# playC.net
KiCad netlist of a schematic drawn in Altium Designer
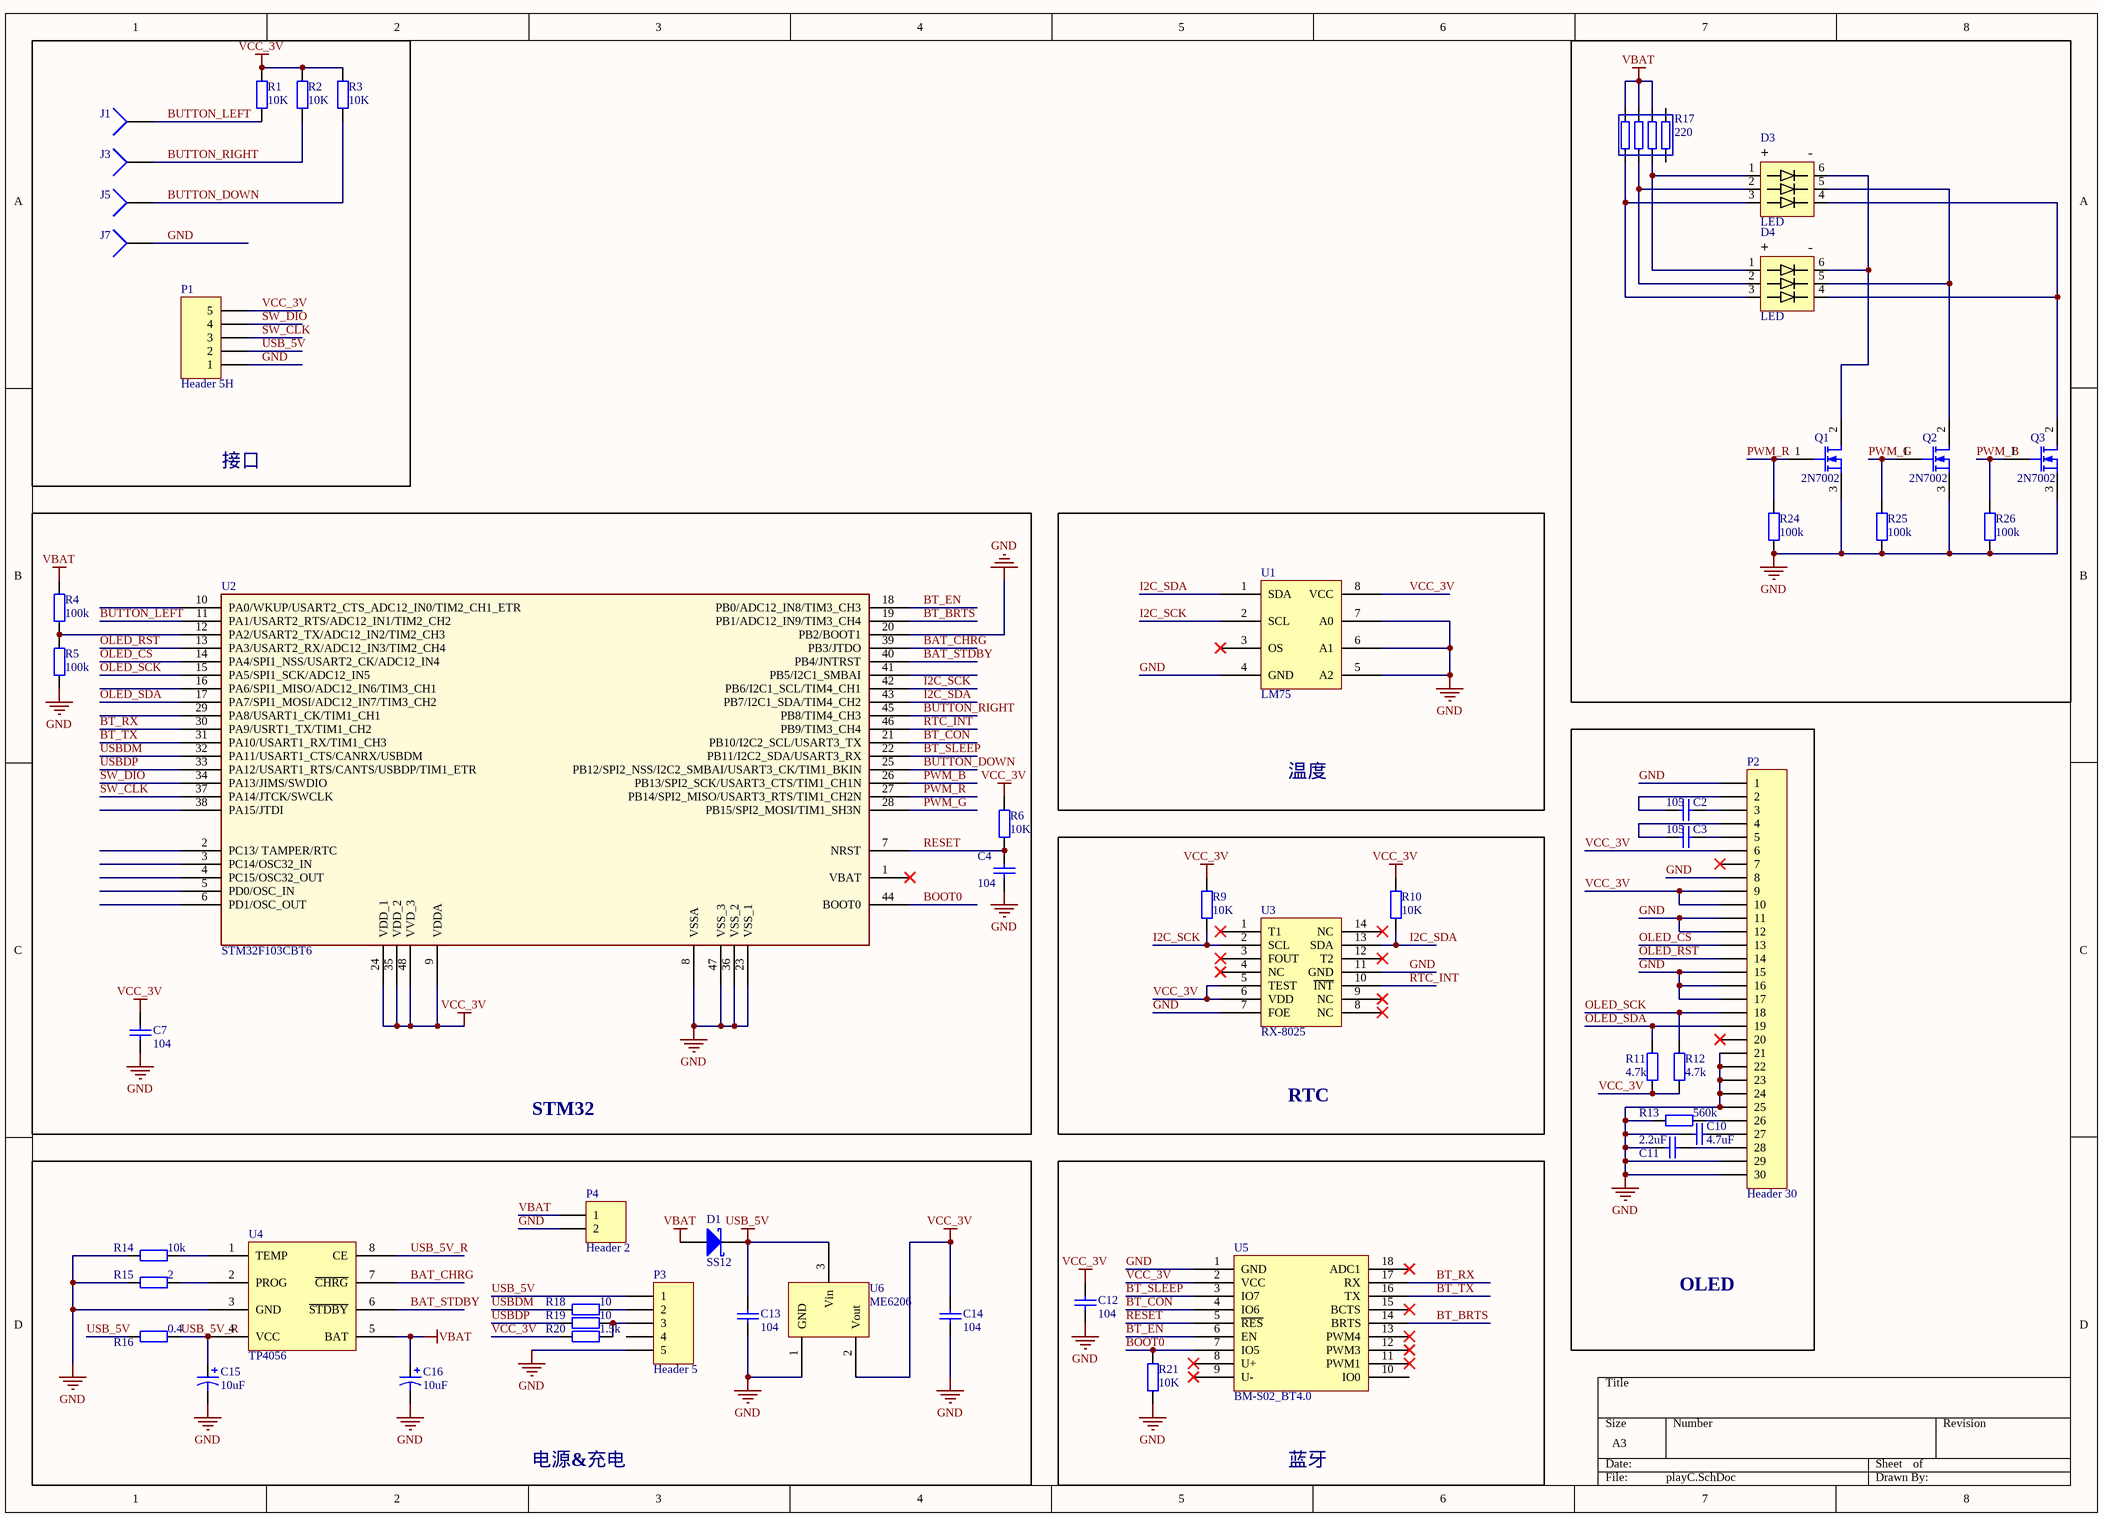
[diagram p0: playC.SchDoc]

(export (version "E")
  (design (tool "Eeschema 10.0.6"))
  (components
    (comp (ref "C2")
      (value "105")
      (footprint "0603")
      (description "Capacitor")
      (fields (field (name "PUBLISHER") "Altium Limited"))
      (libsource (lib "Miscellaneous Devices") (part "Cap"))
    )
    (comp (ref "C3")
      (value "105")
      (footprint "0603")
      (description "Capacitor")
      (fields (field (name "PUBLISHER") "Altium Limited"))
      (libsource (lib "Miscellaneous Devices") (part "Cap"))
    )
    (comp (ref "C4")
      (value "104")
      (footprint "0603")
      (description "Capacitor")
      (fields (field (name "PUBLISHER") "Altium Limited"))
      (libsource (lib "Miscellaneous Devices") (part "Cap"))
    )
    (comp (ref "C7")
      (value "104")
      (footprint "0603")
      (description "Capacitor")
      (fields (field (name "PUBLISHER") "Altium Limited"))
      (libsource (lib "Miscellaneous Devices") (part "Cap"))
    )
    (comp (ref "C10")
      (value "4.7uF")
      (footprint "0805")
      (description "Capacitor")
      (fields (field (name "PUBLISHER") "Altium Limited"))
      (libsource (lib "Miscellaneous Devices") (part "Cap"))
    )
    (comp (ref "C11")
      (value "2.2uF")
      (footprint "0805")
      (description "Capacitor")
      (fields (field (name "PUBLISHER") "Altium Limited"))
      (libsource (lib "Miscellaneous Devices") (part "Cap"))
    )
    (comp (ref "C12")
      (value "104")
      (footprint "0603")
      (description "Capacitor")
      (fields (field (name "PUBLISHER") "Altium Limited"))
      (libsource (lib "Miscellaneous Devices") (part "Cap"))
    )
    (comp (ref "C13")
      (value "104")
      (footprint "0603")
      (description "Capacitor")
      (fields (field (name "PUBLISHER") "Altium Limited"))
      (libsource (lib "Miscellaneous Devices") (part "Cap"))
    )
    (comp (ref "C14")
      (value "104")
      (footprint "0603")
      (description "Capacitor")
      (fields (field (name "PUBLISHER") "Altium Limited"))
      (libsource (lib "Miscellaneous Devices") (part "Cap"))
    )
    (comp (ref "C15")
      (value "10uF")
      (footprint "Cap_Tan_B")
      (description "Polarized Capacitor (Radial)")
      (fields (field (name "PUBLISHER") "Altium Limited"))
      (libsource (lib "Miscellaneous Devices") (part "Cap Pol1"))
    )
    (comp (ref "C16")
      (value "10uF")
      (footprint "Cap_Tan_B")
      (description "Polarized Capacitor (Radial)")
      (fields (field (name "PUBLISHER") "Altium Limited"))
      (libsource (lib "Miscellaneous Devices") (part "Cap Pol1"))
    )
    (comp (ref "D1")
      (value "SS12")
      (footprint "SMA")
      (description "Schottky Diode")
      (fields (field (name "PUBLISHER") "Altium Limited"))
      (libsource (lib "Miscellaneous Devices") (part "D Schottky"))
    )
    (comp (ref "D3") (value "LED") (footprint "5050_LED") (libsource (lib "SmartLED") (part "LED_6Pin")))
    (comp (ref "D4") (value "LED") (footprint "5050_LED") (libsource (lib "SmartLED") (part "LED_6Pin")))
    (comp (ref "J1")
      (value "PAD")
      (footprint "LINK_HOLE")
      (description "Socket")
      (fields (field (name "PUBLISHER") "Altium Limited"))
      (libsource (lib "Miscellaneous Connectors") (part "Socket"))
    )
    (comp (ref "J3")
      (value "PAD")
      (footprint "LINK_HOLE")
      (description "Socket")
      (fields (field (name "PUBLISHER") "Altium Limited"))
      (libsource (lib "Miscellaneous Connectors") (part "Socket"))
    )
    (comp (ref "J5")
      (value "PAD")
      (footprint "LINK_HOLE")
      (description "Socket")
      (fields (field (name "PUBLISHER") "Altium Limited"))
      (libsource (lib "Miscellaneous Connectors") (part "Socket"))
    )
    (comp (ref "J7")
      (value "PAD")
      (footprint "LINK_HOLE")
      (description "Socket")
      (fields (field (name "PUBLISHER") "Altium Limited"))
      (libsource (lib "Miscellaneous Connectors") (part "Socket"))
    )
    (comp (ref "P1")
      (value "Header 5H")
      (footprint "connect_5pin")
      (description "Header, 5-Pin, Right Angle")
      (fields (field (name "PUBLISHER") "Altium Limited"))
      (libsource (lib "Miscellaneous Connectors") (part "Header 5H"))
    )
    (comp (ref "P2")
      (value "Header 30")
      (footprint "OLED(30PIN_1.3')")
      (description "Header, 30-Pin")
      (fields (field (name "PUBLISHER") "Altium Limited"))
      (libsource (lib "Miscellaneous Connectors") (part "Header 30"))
    )
    (comp (ref "P3")
      (value "Header 5")
      (footprint "Mini_USB_IN")
      (description "Header, 5-Pin")
      (fields (field (name "PUBLISHER") "Altium Limited"))
      (libsource (lib "Miscellaneous Connectors") (part "Header 5"))
    )
    (comp (ref "P4")
      (value "Header 2")
      (footprint "HDR1X2")
      (description "Header, 2-Pin")
      (fields (field (name "PUBLISHER") "Altium Limited"))
      (libsource (lib "Miscellaneous Connectors") (part "Header 2"))
    )
    (comp (ref "Q1")
      (value "2N7002")
      (footprint "SOT23")
      (description "N-Channel MOSFET")
      (fields (field (name "PUBLISHER") "Altium Limited"))
      (libsource (lib "Miscellaneous Devices") (part "MOSFET-N"))
    )
    (comp (ref "Q2")
      (value "2N7002")
      (footprint "SOT23")
      (description "N-Channel MOSFET")
      (fields (field (name "PUBLISHER") "Altium Limited"))
      (libsource (lib "Miscellaneous Devices") (part "MOSFET-N"))
    )
    (comp (ref "Q3")
      (value "2N7002")
      (footprint "SOT23")
      (description "N-Channel MOSFET")
      (fields (field (name "PUBLISHER") "Altium Limited"))
      (libsource (lib "Miscellaneous Devices") (part "MOSFET-N"))
    )
    (comp (ref "R1")
      (value "10K")
      (footprint "0603")
      (description "Resistor")
      (fields (field (name "PUBLISHER") "Altium Limited"))
      (libsource (lib "Miscellaneous Devices") (part "Res2"))
    )
    (comp (ref "R2")
      (value "10K")
      (footprint "0603")
      (description "Resistor")
      (fields (field (name "PUBLISHER") "Altium Limited"))
      (libsource (lib "Miscellaneous Devices") (part "Res2"))
    )
    (comp (ref "R3")
      (value "10K")
      (footprint "0603")
      (description "Resistor")
      (fields (field (name "PUBLISHER") "Altium Limited"))
      (libsource (lib "Miscellaneous Devices") (part "Res2"))
    )
    (comp (ref "R4")
      (value "100k")
      (footprint "0603")
      (description "Resistor")
      (fields (field (name "PUBLISHER") "Altium Limited"))
      (libsource (lib "") (part "Res2_1"))
    )
    (comp (ref "R5")
      (value "100k")
      (footprint "0603")
      (description "Resistor")
      (fields (field (name "PUBLISHER") "Altium Limited"))
      (libsource (lib "") (part "Res2_1"))
    )
    (comp (ref "R6")
      (value "10K")
      (footprint "0603")
      (description "Resistor")
      (fields (field (name "PUBLISHER") "Altium Limited"))
      (libsource (lib "Miscellaneous Devices") (part "Res2"))
    )
    (comp (ref "R9")
      (value "10K")
      (footprint "0603")
      (description "Resistor")
      (fields (field (name "PUBLISHER") "Altium Limited"))
      (libsource (lib "Miscellaneous Devices") (part "Res2"))
    )
    (comp (ref "R10")
      (value "10K")
      (footprint "0603")
      (description "Resistor")
      (fields (field (name "PUBLISHER") "Altium Limited"))
      (libsource (lib "Miscellaneous Devices") (part "Res2"))
    )
    (comp (ref "R11")
      (value "4.7k")
      (footprint "0603")
      (description "Resistor")
      (fields (field (name "PUBLISHER") "Altium Limited"))
      (libsource (lib "") (part "Res2_1"))
    )
    (comp (ref "R12")
      (value "4.7k")
      (footprint "0603")
      (description "Resistor")
      (fields (field (name "PUBLISHER") "Altium Limited"))
      (libsource (lib "") (part "Res2_1"))
    )
    (comp (ref "R13")
      (value "560k")
      (footprint "0603")
      (description "Resistor")
      (fields (field (name "PUBLISHER") "Altium Limited"))
      (libsource (lib "") (part "Res2_2"))
    )
    (comp (ref "R14")
      (value "10k")
      (footprint "0603")
      (description "Resistor")
      (fields (field (name "PUBLISHER") "Altium Limited"))
      (libsource (lib "") (part "Res2_2"))
    )
    (comp (ref "R15")
      (value "2")
      (footprint "0603")
      (description "Resistor")
      (fields (field (name "PUBLISHER") "Altium Limited"))
      (libsource (lib "") (part "Res2_2"))
    )
    (comp (ref "R16")
      (value "0.4")
      (footprint "1206")
      (description "Resistor")
      (fields (field (name "PUBLISHER") "Altium Limited"))
      (libsource (lib "") (part "Res2_2"))
    )
    (comp (ref "R17") (value "220") (footprint "0603_4") (libsource (lib "*") (part "RES_SELF_4")))
    (comp (ref "R18")
      (value "10")
      (footprint "0603")
      (description "Resistor")
      (fields (field (name "PUBLISHER") "Altium Limited"))
      (libsource (lib "") (part "Res2_2"))
    )
    (comp (ref "R19")
      (value "10")
      (footprint "0603")
      (description "Resistor")
      (fields (field (name "PUBLISHER") "Altium Limited"))
      (libsource (lib "") (part "Res2_2"))
    )
    (comp (ref "R20")
      (value "1.5k")
      (footprint "0603")
      (description "Resistor")
      (fields (field (name "PUBLISHER") "Altium Limited"))
      (libsource (lib "") (part "Res2_2"))
    )
    (comp (ref "R21")
      (value "10K")
      (footprint "0603")
      (description "Resistor")
      (fields (field (name "PUBLISHER") "Altium Limited"))
      (libsource (lib "Miscellaneous Devices") (part "Res2"))
    )
    (comp (ref "R24")
      (value "100k")
      (footprint "0603")
      (description "Resistor")
      (fields (field (name "PUBLISHER") "Altium Limited"))
      (libsource (lib "Miscellaneous Devices") (part "Res2"))
    )
    (comp (ref "R25")
      (value "100k")
      (footprint "0603")
      (description "Resistor")
      (fields (field (name "PUBLISHER") "Altium Limited"))
      (libsource (lib "Miscellaneous Devices") (part "Res2"))
    )
    (comp (ref "R26")
      (value "100k")
      (footprint "0603")
      (description "Resistor")
      (fields (field (name "PUBLISHER") "Altium Limited"))
      (libsource (lib "Miscellaneous Devices") (part "Res2"))
    )
    (comp (ref "U1") (value "LM75") (footprint "SOIC-8") (libsource (lib "*") (part "LM75")))
    (comp (ref "U2")
      (value "STM32F103CBT6")
      (footprint "LQFP48_N")
      (libsource (lib "*") (part "STM32F103CBT6"))
    )
    (comp (ref "U3") (value "RX-8025") (footprint "SOP-14") (libsource (lib "*") (part "RX-8025T")))
    (comp (ref "U4") (value "TP4056") (footprint "TP4056") (libsource (lib "SmartLED") (part "TP4056")))
    (comp (ref "U5")
      (value "BM-S02_BT4.0")
      (footprint "BM_S02_Bluetooth4.0")
      (libsource (lib "SmartLED") (part "BM-S02_BT4.0"))
    )
    (comp (ref "U6") (value "ME6206") (footprint "BAT54-S") (libsource (lib "HgLib") (part "ME6206")))
  )
  (nets
    (net (code "1") (name "/BAT_CHRG") (class "Default")
      (node (ref "U2") (pin "39") (pinfunction "PB3/JTDO_39") (pintype "passive"))
      (node (ref "U4") (pin "7") (pinfunction "~{CHRG}_7") (pintype "passive"))
    )
    (net (code "2") (name "/BAT_STDBY") (class "Default")
      (node (ref "U2") (pin "40") (pinfunction "PB4/JNTRST_40") (pintype "passive"))
      (node (ref "U4") (pin "6") (pinfunction "~{STDBY}_6") (pintype "passive"))
    )
    (net (code "3") (name "/BOOT0") (class "Default")
      (node (ref "R21") (pin "2") (pinfunction "2_2") (pintype "passive"))
      (node (ref "U2") (pin "44") (pinfunction "BOOT0_44") (pintype "passive"))
      (node (ref "U5") (pin "7") (pinfunction "IO5_7") (pintype "passive"))
    )
    (net (code "4") (name "/BT_BRTS") (class "Default")
      (node (ref "U2") (pin "19") (pinfunction "PB1/ADC12_IN9/TIM3_CH4_19") (pintype "passive"))
      (node (ref "U5") (pin "14") (pinfunction "BRTS_14") (pintype "passive"))
    )
    (net (code "5") (name "/BT_CON") (class "Default")
      (node (ref "U2") (pin "21") (pinfunction "PB10/I2C2_SCL/USART3_TX_21") (pintype "passive"))
      (node (ref "U5") (pin "4") (pinfunction "IO6_4") (pintype "passive"))
    )
    (net (code "6") (name "/BT_EN") (class "Default")
      (node (ref "U2") (pin "18") (pinfunction "PB0/ADC12_IN8/TIM3_CH3_18") (pintype "passive"))
      (node (ref "U5") (pin "6") (pinfunction "EN_6") (pintype "passive"))
    )
    (net (code "7") (name "/BT_RX") (class "Default")
      (node (ref "U2") (pin "30") (pinfunction "PA9/USRT1_TX/TIM1_CH2_30") (pintype "passive"))
      (node (ref "U5") (pin "17") (pinfunction "RX_17") (pintype "passive"))
    )
    (net (code "8") (name "/BT_SLEEP") (class "Default")
      (node (ref "U2") (pin "22") (pinfunction "PB11/I2C2_SDA/USART3_RX_22") (pintype "passive"))
      (node (ref "U5") (pin "3") (pinfunction "IO7_3") (pintype "passive"))
    )
    (net (code "9") (name "/BT_TX") (class "Default")
      (node (ref "U2") (pin "31") (pinfunction "PA10/USART1_RX/TIM1_CH3_31") (pintype "passive"))
      (node (ref "U5") (pin "16") (pinfunction "TX_16") (pintype "passive"))
    )
    (net (code "10") (name "/BUTTON_DOWN") (class "Default")
      (node (ref "J5") (pin "1") (pinfunction "1_1") (pintype "passive"))
      (node (ref "R3") (pin "1") (pinfunction "1_1") (pintype "passive"))
      (node (ref "U2") (pin "25") (pinfunction "PB12/SPI2_NSS/I2C2_SMBAI/USART3_CK/TIM1_BKIN_25") (pintype "passive"))
    )
    (net (code "11") (name "/BUTTON_LEFT") (class "Default")
      (node (ref "J1") (pin "1") (pinfunction "1_1") (pintype "passive"))
      (node (ref "R1") (pin "1") (pinfunction "1_1") (pintype "passive"))
      (node (ref "U2") (pin "11") (pinfunction "PA1/USART2_RTS/ADC12_IN1/TIM2_CH2_11") (pintype "passive"))
    )
    (net (code "12") (name "/BUTTON_RIGHT") (class "Default")
      (node (ref "J3") (pin "1") (pinfunction "1_1") (pintype "passive"))
      (node (ref "R2") (pin "1") (pinfunction "1_1") (pintype "passive"))
      (node (ref "U2") (pin "45") (pinfunction "PB8/TIM4_CH3_45") (pintype "passive"))
    )
    (net (code "13") (name "/I2C_SCK") (class "Default")
      (node (ref "R9") (pin "1") (pinfunction "1_1") (pintype "passive"))
      (node (ref "U1") (pin "2") (pinfunction "SCL_2") (pintype "passive"))
      (node (ref "U2") (pin "42") (pinfunction "PB6/I2C1_SCL/TIM4_CH1_42") (pintype "passive"))
      (node (ref "U3") (pin "2") (pinfunction "SCL_2") (pintype "passive"))
    )
    (net (code "14") (name "/I2C_SDA") (class "Default")
      (node (ref "R10") (pin "1") (pinfunction "1_1") (pintype "passive"))
      (node (ref "U1") (pin "1") (pinfunction "SDA_1") (pintype "passive"))
      (node (ref "U2") (pin "43") (pinfunction "PB7/I2C1_SDA/TIM4_CH2_43") (pintype "passive"))
      (node (ref "U3") (pin "13") (pinfunction "SDA_13") (pintype "passive"))
    )
    (net (code "15") (name "/OLED_CS") (class "Default")
      (node (ref "P2") (pin "13") (pinfunction "13_13") (pintype "passive"))
      (node (ref "U2") (pin "14") (pinfunction "PA4/SPI1_NSS/USART2_CK/ADC12_IN4_14") (pintype "passive"))
    )
    (net (code "16") (name "/OLED_RST") (class "Default")
      (node (ref "P2") (pin "14") (pinfunction "14_14") (pintype "passive"))
      (node (ref "U2") (pin "13") (pinfunction "PA3/USART2_RX/ADC12_IN3/TIM2_CH4_13") (pintype "passive"))
    )
    (net (code "17") (name "/OLED_SCK") (class "Default")
      (node (ref "P2") (pin "18") (pinfunction "18_18") (pintype "passive"))
      (node (ref "R12") (pin "1") (pinfunction "1_1") (pintype "passive"))
      (node (ref "U2") (pin "15") (pinfunction "PA5/SPI1_SCK/ADC12_IN5_15") (pintype "passive"))
    )
    (net (code "18") (name "/OLED_SDA") (class "Default")
      (node (ref "P2") (pin "19") (pinfunction "19_19") (pintype "passive"))
      (node (ref "R11") (pin "1") (pinfunction "1_1") (pintype "passive"))
      (node (ref "U2") (pin "17") (pinfunction "PA7/SPI1_MOSI/ADC12_IN7/TIM3_CH2_17") (pintype "passive"))
    )
    (net (code "19") (name "/PWM_B") (class "Default")
      (node (ref "Q3") (pin "1") (pinfunction "G_1") (pintype "passive"))
      (node (ref "R26") (pin "2") (pinfunction "2_2") (pintype "passive"))
      (node (ref "U2") (pin "26") (pinfunction "PB13/SPI2_SCK/USART3_CTS/TIM1_CH1N_26") (pintype "passive"))
    )
    (net (code "20") (name "/PWM_G") (class "Default")
      (node (ref "Q2") (pin "1") (pinfunction "G_1") (pintype "passive"))
      (node (ref "R25") (pin "2") (pinfunction "2_2") (pintype "passive"))
      (node (ref "U2") (pin "28") (pinfunction "PB15/SPI2_MOSI/TIM1_SH3N_28") (pintype "passive"))
    )
    (net (code "21") (name "/PWM_R") (class "Default")
      (node (ref "Q1") (pin "1") (pinfunction "G_1") (pintype "passive"))
      (node (ref "R24") (pin "2") (pinfunction "2_2") (pintype "passive"))
      (node (ref "U2") (pin "27") (pinfunction "PB14/SPI2_MISO/USART3_RTS/TIM1_CH2N_27") (pintype "passive"))
    )
    (net (code "22") (name "/RESET") (class "Default")
      (node (ref "C4") (pin "2") (pinfunction "2_2") (pintype "passive"))
      (node (ref "R6") (pin "1") (pinfunction "1_1") (pintype "passive"))
      (node (ref "U2") (pin "7") (pinfunction "NRST_7") (pintype "passive"))
      (node (ref "U5") (pin "5") (pinfunction "~{RES}_5") (pintype "passive"))
    )
    (net (code "23") (name "/RTC_INT") (class "Default")
      (node (ref "U2") (pin "46") (pinfunction "PB9/TIM3_CH4_46") (pintype "passive"))
      (node (ref "U3") (pin "10") (pinfunction "~{INT}_10") (pintype "passive"))
    )
    (net (code "24") (name "/SW_CLK") (class "Default")
      (node (ref "P1") (pin "3") (pinfunction "3_3") (pintype "passive"))
      (node (ref "U2") (pin "37") (pinfunction "PA14/JTCK/SWCLK_37") (pintype "passive"))
    )
    (net (code "25") (name "/SW_DIO") (class "Default")
      (node (ref "P1") (pin "4") (pinfunction "4_4") (pintype "passive"))
      (node (ref "U2") (pin "34") (pinfunction "PA13/JIMS/SWDIO_34") (pintype "passive"))
    )
    (net (code "26") (name "/USBDM") (class "Default")
      (node (ref "R18") (pin "2") (pinfunction "2_2") (pintype "passive"))
      (node (ref "U2") (pin "32") (pinfunction "PA11/USART1_CTS/CANRX/USBDM_32") (pintype "passive"))
    )
    (net (code "27") (name "/USBDP") (class "Default")
      (node (ref "R19") (pin "2") (pinfunction "2_2") (pintype "passive"))
      (node (ref "U2") (pin "33") (pinfunction "PA12/USART1_RTS/CANTS/USBDP/TIM1_ETR_33") (pintype "passive"))
    )
    (net (code "28") (name "/USB_5V_R") (class "Default")
      (node (ref "C15") (pin "1") (pinfunction "1_1") (pintype "passive"))
      (node (ref "R16") (pin "1") (pinfunction "1_1") (pintype "passive"))
      (node (ref "U4") (pin "4") (pinfunction "VCC_4") (pintype "passive"))
      (node (ref "U4") (pin "8") (pinfunction "CE_8") (pintype "passive"))
    )
    (net (code "29") (name "GND") (class "Default")
      (node (ref "C10") (pin "2") (pinfunction "2_2") (pintype "passive"))
      (node (ref "C11") (pin "2") (pinfunction "2_2") (pintype "passive"))
      (node (ref "C12") (pin "1") (pinfunction "1_1") (pintype "passive"))
      (node (ref "C13") (pin "1") (pinfunction "1_1") (pintype "passive"))
      (node (ref "C14") (pin "1") (pinfunction "1_1") (pintype "passive"))
      (node (ref "C15") (pin "2") (pinfunction "2_2") (pintype "passive"))
      (node (ref "C16") (pin "2") (pinfunction "2_2") (pintype "passive"))
      (node (ref "C4") (pin "1") (pinfunction "1_1") (pintype "passive"))
      (node (ref "C7") (pin "1") (pinfunction "1_1") (pintype "passive"))
      (node (ref "J7") (pin "1") (pinfunction "1_1") (pintype "passive"))
      (node (ref "P1") (pin "1") (pinfunction "1_1") (pintype "passive"))
      (node (ref "P2") (pin "1") (pinfunction "1_1") (pintype "passive"))
      (node (ref "P2") (pin "11") (pinfunction "11_11") (pintype "passive"))
      (node (ref "P2") (pin "12") (pinfunction "12_12") (pintype "passive"))
      (node (ref "P2") (pin "15") (pinfunction "15_15") (pintype "passive"))
      (node (ref "P2") (pin "16") (pinfunction "16_16") (pintype "passive"))
      (node (ref "P2") (pin "17") (pinfunction "17_17") (pintype "passive"))
      (node (ref "P2") (pin "21") (pinfunction "21_21") (pintype "passive"))
      (node (ref "P2") (pin "22") (pinfunction "22_22") (pintype "passive"))
      (node (ref "P2") (pin "23") (pinfunction "23_23") (pintype "passive"))
      (node (ref "P2") (pin "24") (pinfunction "24_24") (pintype "passive"))
      (node (ref "P2") (pin "25") (pinfunction "25_25") (pintype "passive"))
      (node (ref "P2") (pin "29") (pinfunction "29_29") (pintype "passive"))
      (node (ref "P2") (pin "30") (pinfunction "30_30") (pintype "passive"))
      (node (ref "P2") (pin "8") (pinfunction "8_8") (pintype "passive"))
      (node (ref "P3") (pin "5") (pinfunction "5_5") (pintype "passive"))
      (node (ref "P4") (pin "2") (pinfunction "2_2") (pintype "passive"))
      (node (ref "Q1") (pin "3") (pinfunction "S_3") (pintype "passive"))
      (node (ref "Q2") (pin "3") (pinfunction "S_3") (pintype "passive"))
      (node (ref "Q3") (pin "3") (pinfunction "S_3") (pintype "passive"))
      (node (ref "R13") (pin "2") (pinfunction "2_2") (pintype "passive"))
      (node (ref "R14") (pin "2") (pinfunction "2_2") (pintype "passive"))
      (node (ref "R15") (pin "2") (pinfunction "2_2") (pintype "passive"))
      (node (ref "R21") (pin "1") (pinfunction "1_1") (pintype "passive"))
      (node (ref "R24") (pin "1") (pinfunction "1_1") (pintype "passive"))
      (node (ref "R25") (pin "1") (pinfunction "1_1") (pintype "passive"))
      (node (ref "R26") (pin "1") (pinfunction "1_1") (pintype "passive"))
      (node (ref "R5") (pin "2") (pinfunction "2_2") (pintype "passive"))
      (node (ref "U1") (pin "4") (pinfunction "GND_4") (pintype "passive"))
      (node (ref "U1") (pin "5") (pinfunction "A2_5") (pintype "passive"))
      (node (ref "U1") (pin "6") (pinfunction "A1_6") (pintype "passive"))
      (node (ref "U1") (pin "7") (pinfunction "A0_7") (pintype "passive"))
      (node (ref "U2") (pin "20") (pinfunction "PB2/BOOT1_20") (pintype "passive"))
      (node (ref "U2") (pin "23") (pinfunction "VSS_1_23") (pintype "passive"))
      (node (ref "U2") (pin "36") (pinfunction "VSS_2_36") (pintype "passive"))
      (node (ref "U2") (pin "47") (pinfunction "VSS_3_47") (pintype "passive"))
      (node (ref "U2") (pin "8") (pinfunction "VSSA_8") (pintype "passive"))
      (node (ref "U3") (pin "11") (pinfunction "GND_11") (pintype "passive"))
      (node (ref "U3") (pin "7") (pinfunction "FOE_7") (pintype "passive"))
      (node (ref "U4") (pin "3") (pinfunction "GND_3") (pintype "passive"))
      (node (ref "U5") (pin "1") (pinfunction "GND_1") (pintype "passive"))
      (node (ref "U6") (pin "1") (pinfunction "GND_1") (pintype "passive"))
    )
    (net (code "30") (name "Net-(C2-Pad1)") (class "Default")
      (node (ref "C2") (pin "1") (pinfunction "1_1") (pintype "passive"))
      (node (ref "P2") (pin "3") (pinfunction "3_3") (pintype "passive"))
    )
    (net (code "31") (name "Net-(C2-Pad2)") (class "Default")
      (node (ref "C2") (pin "2") (pinfunction "2_2") (pintype "passive"))
      (node (ref "P2") (pin "2") (pinfunction "2_2") (pintype "passive"))
    )
    (net (code "32") (name "Net-(C3-Pad1)") (class "Default")
      (node (ref "C3") (pin "1") (pinfunction "1_1") (pintype "passive"))
      (node (ref "P2") (pin "5") (pinfunction "5_5") (pintype "passive"))
    )
    (net (code "33") (name "Net-(C3-Pad2)") (class "Default")
      (node (ref "C3") (pin "2") (pinfunction "2_2") (pintype "passive"))
      (node (ref "P2") (pin "4") (pinfunction "4_4") (pintype "passive"))
    )
    (net (code "34") (name "Net-(C10-Pad1)") (class "Default")
      (node (ref "C10") (pin "1") (pinfunction "1_1") (pintype "passive"))
      (node (ref "P2") (pin "27") (pinfunction "27_27") (pintype "passive"))
    )
    (net (code "35") (name "Net-(C11-Pad1)") (class "Default")
      (node (ref "C11") (pin "1") (pinfunction "1_1") (pintype "passive"))
      (node (ref "P2") (pin "28") (pinfunction "28_28") (pintype "passive"))
    )
    (net (code "36") (name "Net-(D3-Pad1)") (class "Default")
      (node (ref "D3") (pin "1") (pinfunction "1_1") (pintype "passive"))
      (node (ref "D4") (pin "1") (pinfunction "1_1") (pintype "passive"))
      (node (ref "R17") (pin "2") (pinfunction "2_2") (pintype "passive"))
    )
    (net (code "37") (name "Net-(D3-Pad2)") (class "Default")
      (node (ref "D3") (pin "2") (pinfunction "2_2") (pintype "passive"))
      (node (ref "D4") (pin "2") (pinfunction "2_2") (pintype "passive"))
      (node (ref "R17") (pin "3") (pinfunction "3_3") (pintype "passive"))
    )
    (net (code "38") (name "Net-(D3-Pad3)") (class "Default")
      (node (ref "D3") (pin "3") (pinfunction "3_3") (pintype "passive"))
      (node (ref "D4") (pin "3") (pinfunction "3_3") (pintype "passive"))
      (node (ref "R17") (pin "4") (pinfunction "4_4") (pintype "passive"))
    )
    (net (code "39") (name "Net-(P2-Pad26)") (class "Default")
      (node (ref "P2") (pin "26") (pinfunction "26_26") (pintype "passive"))
      (node (ref "R13") (pin "1") (pinfunction "1_1") (pintype "passive"))
    )
    (net (code "40") (name "Net-(P3-Pad2)") (class "Default")
      (node (ref "P3") (pin "2") (pinfunction "2_2") (pintype "passive"))
      (node (ref "R18") (pin "1") (pinfunction "1_1") (pintype "passive"))
    )
    (net (code "41") (name "Net-(P3-Pad3)") (class "Default")
      (node (ref "P3") (pin "3") (pinfunction "3_3") (pintype "passive"))
      (node (ref "R19") (pin "1") (pinfunction "1_1") (pintype "passive"))
      (node (ref "R20") (pin "1") (pinfunction "1_1") (pintype "passive"))
    )
    (net (code "42") (name "Net-(Q1-D)") (class "Default")
      (node (ref "D3") (pin "6") (pinfunction "6_6") (pintype "passive"))
      (node (ref "D4") (pin "6") (pinfunction "6_6") (pintype "passive"))
      (node (ref "Q1") (pin "2") (pinfunction "D_2") (pintype "passive"))
    )
    (net (code "43") (name "Net-(Q2-D)") (class "Default")
      (node (ref "D3") (pin "5") (pinfunction "5_5") (pintype "passive"))
      (node (ref "D4") (pin "5") (pinfunction "5_5") (pintype "passive"))
      (node (ref "Q2") (pin "2") (pinfunction "D_2") (pintype "passive"))
    )
    (net (code "44") (name "Net-(Q3-D)") (class "Default")
      (node (ref "D3") (pin "4") (pinfunction "4_4") (pintype "passive"))
      (node (ref "D4") (pin "4") (pinfunction "4_4") (pintype "passive"))
      (node (ref "Q3") (pin "2") (pinfunction "D_2") (pintype "passive"))
    )
    (net (code "45") (name "Net-(U2-PA2{slash}USART2_TX{slash}ADC12_IN2{slash}TIM2_CH3)") (class "Default")
      (node (ref "R4") (pin "2") (pinfunction "2_2") (pintype "passive"))
      (node (ref "R5") (pin "1") (pinfunction "1_1") (pintype "passive"))
      (node (ref "U2") (pin "12") (pinfunction "PA2/USART2_TX/ADC12_IN2/TIM2_CH3_12") (pintype "passive"))
    )
    (net (code "46") (name "Net-(U4-PROG)") (class "Default")
      (node (ref "R15") (pin "1") (pinfunction "1_1") (pintype "passive"))
      (node (ref "U4") (pin "2") (pinfunction "PROG_2") (pintype "passive"))
    )
    (net (code "47") (name "Net-(U4-TEMP)") (class "Default")
      (node (ref "R14") (pin "1") (pinfunction "1_1") (pintype "passive"))
      (node (ref "U4") (pin "1") (pinfunction "TEMP_1") (pintype "passive"))
    )
    (net (code "48") (name "USB_5V") (class "Default")
      (node (ref "C13") (pin "2") (pinfunction "2_2") (pintype "passive"))
      (node (ref "D1") (pin "2") (pinfunction "K_2") (pintype "passive"))
      (node (ref "P1") (pin "2") (pinfunction "2_2") (pintype "passive"))
      (node (ref "P3") (pin "1") (pinfunction "1_1") (pintype "passive"))
      (node (ref "R16") (pin "2") (pinfunction "2_2") (pintype "passive"))
      (node (ref "U6") (pin "3") (pinfunction "Vin_3") (pintype "passive"))
    )
    (net (code "49") (name "VBAT") (class "Default")
      (node (ref "C16") (pin "1") (pinfunction "1_1") (pintype "passive"))
      (node (ref "D1") (pin "1") (pinfunction "A_1") (pintype "passive"))
      (node (ref "P4") (pin "1") (pinfunction "1_1") (pintype "passive"))
      (node (ref "R17") (pin "5") (pinfunction "5_5") (pintype "passive"))
      (node (ref "R17") (pin "6") (pinfunction "6_6") (pintype "passive"))
      (node (ref "R17") (pin "7") (pinfunction "7_7") (pintype "passive"))
      (node (ref "R4") (pin "1") (pinfunction "1_1") (pintype "passive"))
      (node (ref "U4") (pin "5") (pinfunction "BAT_5") (pintype "passive"))
    )
    (net (code "50") (name "VCC_3V") (class "Default")
      (node (ref "C12") (pin "2") (pinfunction "2_2") (pintype "passive"))
      (node (ref "C14") (pin "2") (pinfunction "2_2") (pintype "passive"))
      (node (ref "C7") (pin "2") (pinfunction "2_2") (pintype "passive"))
      (node (ref "P1") (pin "5") (pinfunction "5_5") (pintype "passive"))
      (node (ref "P2") (pin "10") (pinfunction "10_10") (pintype "passive"))
      (node (ref "P2") (pin "6") (pinfunction "6_6") (pintype "passive"))
      (node (ref "P2") (pin "9") (pinfunction "9_9") (pintype "passive"))
      (node (ref "R1") (pin "2") (pinfunction "2_2") (pintype "passive"))
      (node (ref "R10") (pin "2") (pinfunction "2_2") (pintype "passive"))
      (node (ref "R11") (pin "2") (pinfunction "2_2") (pintype "passive"))
      (node (ref "R12") (pin "2") (pinfunction "2_2") (pintype "passive"))
      (node (ref "R2") (pin "2") (pinfunction "2_2") (pintype "passive"))
      (node (ref "R20") (pin "2") (pinfunction "2_2") (pintype "passive"))
      (node (ref "R3") (pin "2") (pinfunction "2_2") (pintype "passive"))
      (node (ref "R6") (pin "2") (pinfunction "2_2") (pintype "passive"))
      (node (ref "R9") (pin "2") (pinfunction "2_2") (pintype "passive"))
      (node (ref "U1") (pin "8") (pinfunction "VCC_8") (pintype "passive"))
      (node (ref "U2") (pin "24") (pinfunction "VDD_1_24") (pintype "passive"))
      (node (ref "U2") (pin "35") (pinfunction "VDD_2_35") (pintype "passive"))
      (node (ref "U2") (pin "48") (pinfunction "VVD_3_48") (pintype "passive"))
      (node (ref "U2") (pin "9") (pinfunction "VDDA_9") (pintype "passive"))
      (node (ref "U3") (pin "5") (pinfunction "TEST_5") (pintype "passive"))
      (node (ref "U3") (pin "6") (pinfunction "VDD_6") (pintype "passive"))
      (node (ref "U5") (pin "2") (pinfunction "VCC_2") (pintype "passive"))
      (node (ref "U6") (pin "2") (pinfunction "Vout_2") (pintype "passive"))
    )
    (net (code "51") (name "unconnected-(P2-Pad7)") (class "Default")
      (node (ref "P2") (pin "7") (pinfunction "7_7") (pintype "passive+no_connect"))
    )
    (net (code "52") (name "unconnected-(P2-Pad20)") (class "Default")
      (node (ref "P2") (pin "20") (pinfunction "20_20") (pintype "passive+no_connect"))
    )
    (net (code "53") (name "unconnected-(P3-Pad4)") (class "Default")
      (node (ref "P3") (pin "4") (pinfunction "4_4") (pintype "passive"))
    )
    (net (code "54") (name "unconnected-(R17-Pad1)") (class "Default")
      (node (ref "R17") (pin "1") (pinfunction "1_1") (pintype "passive"))
    )
    (net (code "55") (name "unconnected-(R17-Pad8)") (class "Default")
      (node (ref "R17") (pin "8") (pinfunction "8_8") (pintype "passive"))
    )
    (net (code "56") (name "unconnected-(U1-OS-Pad3)") (class "Default")
      (node (ref "U1") (pin "3") (pinfunction "OS_3") (pintype "passive+no_connect"))
    )
    (net (code "57") (name "unconnected-(U2-PA0{slash}WKUP{slash}USART2_CTS_ADC12_IN0{slash}TIM2_CH1_ETR-Pad10)") (class "Default")
      (node (ref "U2") (pin "10") (pinfunction "PA0/WKUP/USART2_CTS_ADC12_IN0/TIM2_CH1_ETR_10") (pintype "passive"))
    )
    (net (code "58") (name "unconnected-(U2-PA6{slash}SPI1_MISO{slash}ADC12_IN6{slash}TIM3_CH1-Pad16)") (class "Default")
      (node (ref "U2") (pin "16") (pinfunction "PA6/SPI1_MISO/ADC12_IN6/TIM3_CH1_16") (pintype "passive"))
    )
    (net (code "59") (name "unconnected-(U2-PA8{slash}USART1_CK{slash}TIM1_CH1-Pad29)") (class "Default")
      (node (ref "U2") (pin "29") (pinfunction "PA8/USART1_CK/TIM1_CH1_29") (pintype "passive"))
    )
    (net (code "60") (name "unconnected-(U2-PA15{slash}JTDI-Pad38)") (class "Default")
      (node (ref "U2") (pin "38") (pinfunction "PA15/JTDI_38") (pintype "passive"))
    )
    (net (code "61") (name "unconnected-(U2-PB5{slash}I2C1_SMBAI-Pad41)") (class "Default")
      (node (ref "U2") (pin "41") (pinfunction "PB5/I2C1_SMBAI_41") (pintype "passive"))
    )
    (net (code "62") (name "unconnected-(U2-PC13{slash}_TAMPER{slash}RTC-Pad2)") (class "Default")
      (node (ref "U2") (pin "2") (pinfunction "PC13/_TAMPER/RTC_2") (pintype "passive"))
    )
    (net (code "63") (name "unconnected-(U2-PC14{slash}OSC32_IN-Pad3)") (class "Default")
      (node (ref "U2") (pin "3") (pinfunction "PC14/OSC32_IN_3") (pintype "passive"))
    )
    (net (code "64") (name "unconnected-(U2-PC15{slash}OSC32_OUT-Pad4)") (class "Default")
      (node (ref "U2") (pin "4") (pinfunction "PC15/OSC32_OUT_4") (pintype "passive"))
    )
    (net (code "65") (name "unconnected-(U2-PD0{slash}OSC_IN-Pad5)") (class "Default")
      (node (ref "U2") (pin "5") (pinfunction "PD0/OSC_IN_5") (pintype "passive"))
    )
    (net (code "66") (name "unconnected-(U2-PD1{slash}OSC_OUT-Pad6)") (class "Default")
      (node (ref "U2") (pin "6") (pinfunction "PD1/OSC_OUT_6") (pintype "passive"))
    )
    (net (code "67") (name "unconnected-(U2-VBAT-Pad1)") (class "Default")
      (node (ref "U2") (pin "1") (pinfunction "VBAT_1") (pintype "passive+no_connect"))
    )
    (net (code "68") (name "unconnected-(U3-FOUT-Pad3)") (class "Default")
      (node (ref "U3") (pin "3") (pinfunction "FOUT_3") (pintype "passive+no_connect"))
    )
    (net (code "69") (name "unconnected-(U3-NC-Pad4)") (class "Default")
      (node (ref "U3") (pin "4") (pinfunction "NC_4") (pintype "passive+no_connect"))
    )
    (net (code "70") (name "unconnected-(U3-NC-Pad8)") (class "Default")
      (node (ref "U3") (pin "8") (pinfunction "NC_8") (pintype "passive+no_connect"))
    )
    (net (code "71") (name "unconnected-(U3-NC-Pad9)") (class "Default")
      (node (ref "U3") (pin "9") (pinfunction "NC_9") (pintype "passive+no_connect"))
    )
    (net (code "72") (name "unconnected-(U3-NC-Pad14)") (class "Default")
      (node (ref "U3") (pin "14") (pinfunction "NC_14") (pintype "passive+no_connect"))
    )
    (net (code "73") (name "unconnected-(U3-T1-Pad1)") (class "Default")
      (node (ref "U3") (pin "1") (pinfunction "T1_1") (pintype "passive+no_connect"))
    )
    (net (code "74") (name "unconnected-(U3-T2-Pad12)") (class "Default")
      (node (ref "U3") (pin "12") (pinfunction "T2_12") (pintype "passive+no_connect"))
    )
    (net (code "75") (name "unconnected-(U5-ADC1-Pad18)") (class "Default")
      (node (ref "U5") (pin "18") (pinfunction "ADC1_18") (pintype "passive+no_connect"))
    )
    (net (code "76") (name "unconnected-(U5-BCTS-Pad15)") (class "Default")
      (node (ref "U5") (pin "15") (pinfunction "BCTS_15") (pintype "passive+no_connect"))
    )
    (net (code "77") (name "unconnected-(U5-IO0-Pad10)") (class "Default")
      (node (ref "U5") (pin "10") (pinfunction "IO0_10") (pintype "passive"))
    )
    (net (code "78") (name "unconnected-(U5-PWM1-Pad11)") (class "Default")
      (node (ref "U5") (pin "11") (pinfunction "PWM1_11") (pintype "passive+no_connect"))
    )
    (net (code "79") (name "unconnected-(U5-PWM3-Pad12)") (class "Default")
      (node (ref "U5") (pin "12") (pinfunction "PWM3_12") (pintype "passive+no_connect"))
    )
    (net (code "80") (name "unconnected-(U5-PWM4-Pad13)") (class "Default")
      (node (ref "U5") (pin "13") (pinfunction "PWM4_13") (pintype "passive+no_connect"))
    )
    (net (code "81") (name "unconnected-(U5-U+-Pad8)") (class "Default")
      (node (ref "U5") (pin "8") (pinfunction "U+_8") (pintype "passive+no_connect"))
    )
    (net (code "82") (name "unconnected-(U5-U--Pad9)") (class "Default")
      (node (ref "U5") (pin "9") (pinfunction "U-_9") (pintype "passive+no_connect"))
    )
  )
)
